# schematic_r2.net
KiCad netlist of a schematic drawn in EAGLE
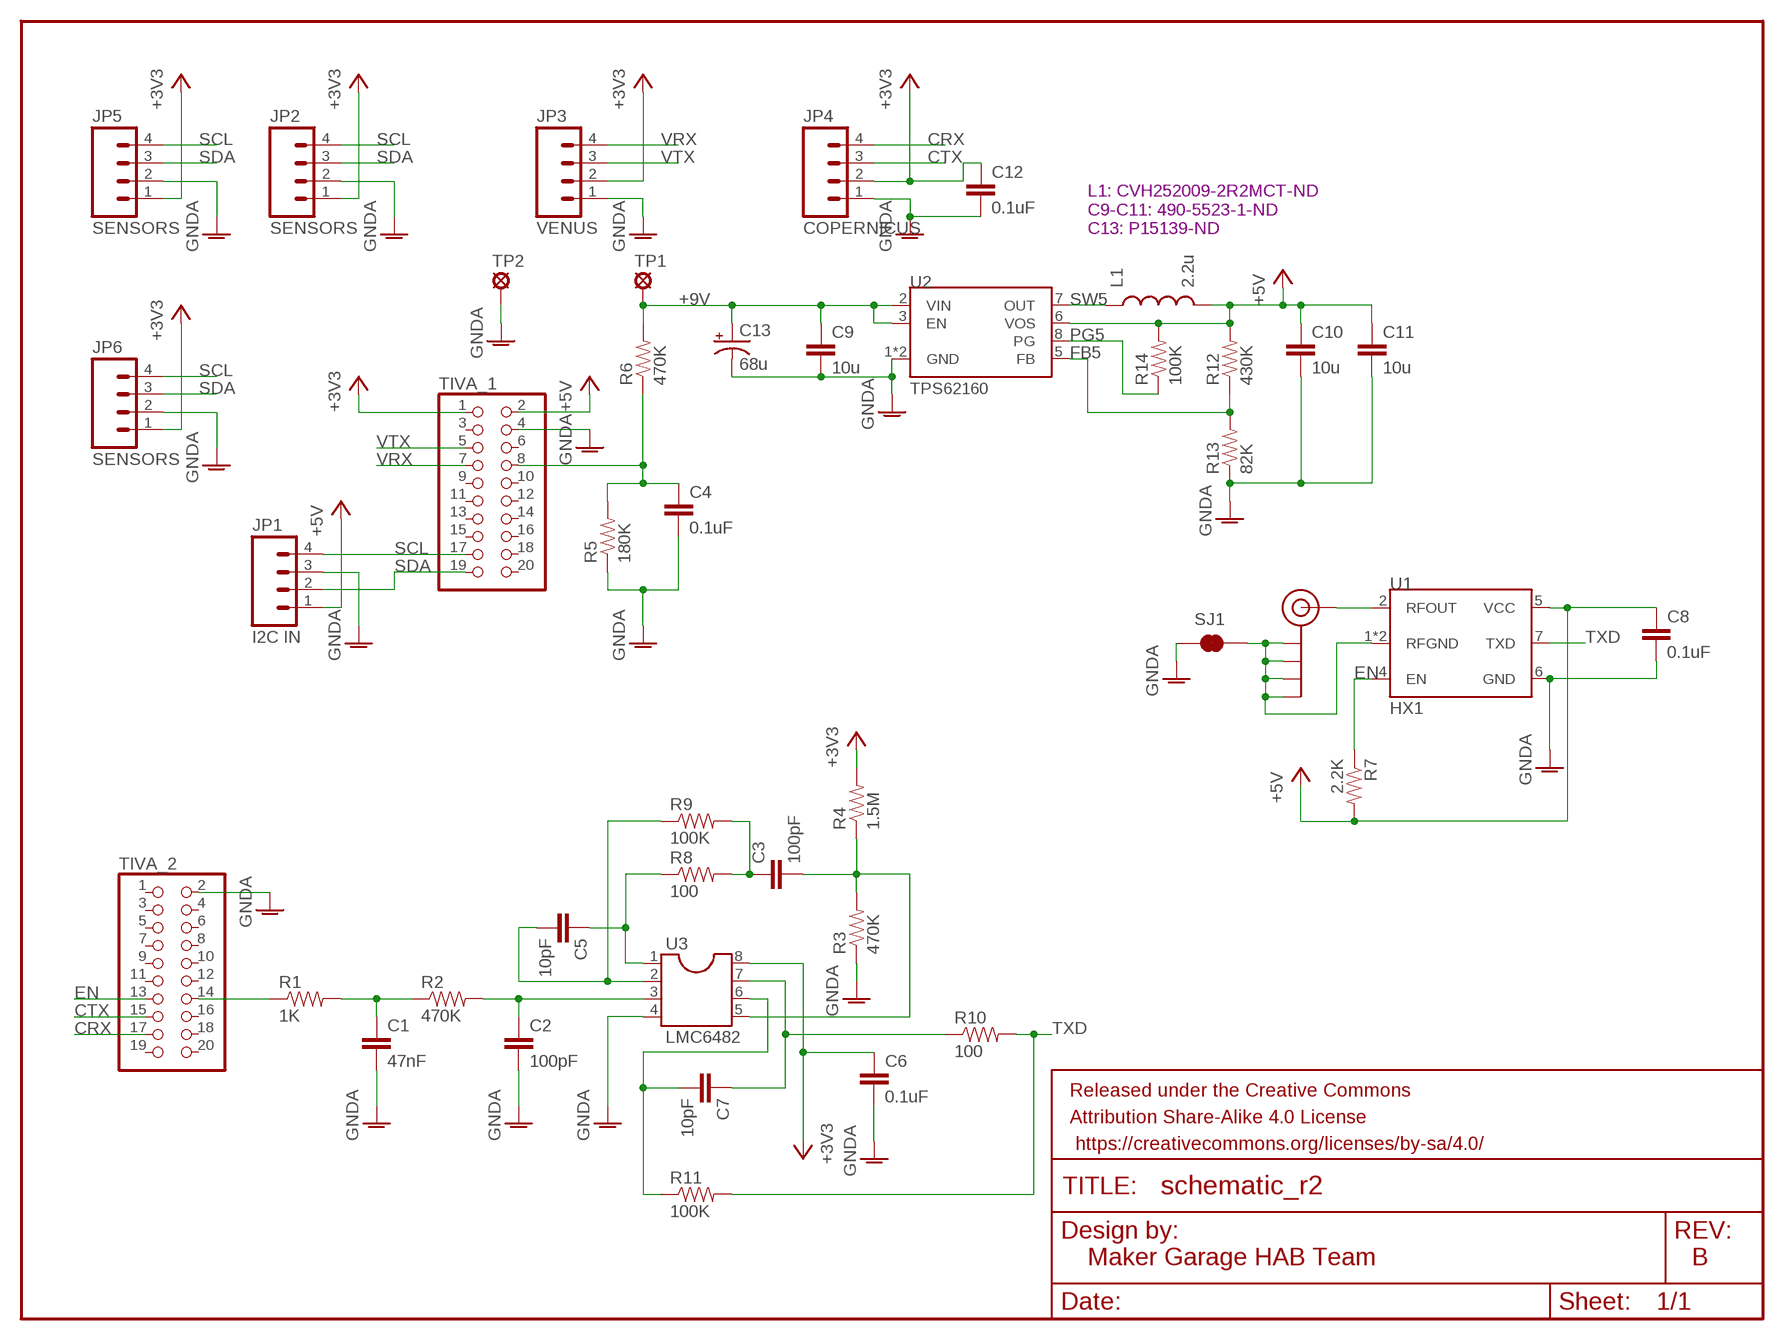
[diagram p0: schematic, sheet 1]

(export (version "E")
  (design (tool "Eeschema 10.0.6"))
  (components
    (comp (ref "C1")
      (value "47nF")
      (footprint "eagle-import:0805")
      (libsource (lib "eagle-import") (part "CAP0805"))
    )
    (comp (ref "C2")
      (value "100pF")
      (footprint "eagle-import:0805")
      (libsource (lib "eagle-import") (part "CAP0805"))
    )
    (comp (ref "C3")
      (value "100pF")
      (footprint "eagle-import:0805")
      (libsource (lib "eagle-import") (part "CAP0805"))
    )
    (comp (ref "C4")
      (value "0.1uF")
      (footprint "eagle-import:0805")
      (libsource (lib "eagle-import") (part "CAP0805"))
    )
    (comp (ref "C5")
      (value "10pF")
      (footprint "eagle-import:0805")
      (libsource (lib "eagle-import") (part "CAP0805"))
    )
    (comp (ref "C6")
      (value "0.1uF")
      (footprint "eagle-import:0805")
      (libsource (lib "eagle-import") (part "CAP0805"))
    )
    (comp (ref "C7")
      (value "10pF")
      (footprint "eagle-import:0805")
      (libsource (lib "eagle-import") (part "CAP0805"))
    )
    (comp (ref "C8")
      (value "0.1uF")
      (footprint "eagle-import:0805")
      (libsource (lib "eagle-import") (part "CAP0805"))
    )
    (comp (ref "C9")
      (value "10u")
      (footprint "eagle-import:0805")
      (libsource (lib "eagle-import") (part "CAP0805"))
    )
    (comp (ref "C10")
      (value "10u")
      (footprint "eagle-import:0805")
      (libsource (lib "eagle-import") (part "CAP0805"))
    )
    (comp (ref "C11")
      (value "10u")
      (footprint "eagle-import:0805")
      (libsource (lib "eagle-import") (part "CAP0805"))
    )
    (comp (ref "C12")
      (value "0.1uF")
      (footprint "eagle-import:0805")
      (libsource (lib "eagle-import") (part "CAP0805"))
    )
    (comp (ref "C13")
      (value "68u")
      (footprint "eagle-import:CPOL-RADIAL-10UF-25V")
      (libsource (lib "eagle-import") (part "CAP_POLPTH2"))
    )
    (comp (ref "FRAME1")
      (value "FRAME-LETTERNO_PACKAGE")
      (footprint "eagle-import:DUMMY")
      (fields (field (name "DESIGNER") "Nobody"))
      (libsource (lib "eagle-import") (part "FRAME-LETTERNO_PACKAGE"))
    )
    (comp (ref "J1")
      (value "SMA_EDGE")
      (footprint "eagle-import:SMA-EDGE")
      (libsource (lib "eagle-import") (part "SMA_EDGE"))
    )
    (comp (ref "JP1")
      (value "I2C IN")
      (footprint "eagle-import:1X04")
      (libsource (lib "eagle-import") (part "M04PTH"))
    )
    (comp (ref "JP2")
      (value "SENSORS")
      (footprint "eagle-import:1X04")
      (libsource (lib "eagle-import") (part "M04PTH"))
    )
    (comp (ref "JP3")
      (value "VENUS")
      (footprint "eagle-import:1X04")
      (libsource (lib "eagle-import") (part "M04PTH"))
    )
    (comp (ref "JP4")
      (value "COPERNICUS")
      (footprint "eagle-import:1X04")
      (libsource (lib "eagle-import") (part "M04PTH"))
    )
    (comp (ref "JP5")
      (value "SENSORS")
      (footprint "eagle-import:1X04")
      (libsource (lib "eagle-import") (part "M04PTH"))
    )
    (comp (ref "JP6")
      (value "SENSORS")
      (footprint "eagle-import:1X04")
      (libsource (lib "eagle-import") (part "M04PTH"))
    )
    (comp (ref "L1")
      (value "2.2u")
      (footprint "eagle-import:1008")
      (libsource (lib "eagle-import") (part "INDUCTOR1008"))
    )
    (comp (ref "R1")
      (value "1K")
      (footprint "eagle-import:0805")
      (libsource (lib "eagle-import") (part "RESISTOR0805-RES"))
    )
    (comp (ref "R2")
      (value "470K")
      (footprint "eagle-import:0805")
      (libsource (lib "eagle-import") (part "RESISTOR0805-RES"))
    )
    (comp (ref "R3")
      (value "470K")
      (footprint "eagle-import:0805")
      (libsource (lib "eagle-import") (part "RESISTOR0805-RES"))
    )
    (comp (ref "R4")
      (value "1.5M")
      (footprint "eagle-import:0805")
      (libsource (lib "eagle-import") (part "RESISTOR0805-RES"))
    )
    (comp (ref "R5")
      (value "180K")
      (footprint "eagle-import:0805")
      (libsource (lib "eagle-import") (part "RESISTOR0805-RES"))
    )
    (comp (ref "R6")
      (value "470K")
      (footprint "eagle-import:0805")
      (libsource (lib "eagle-import") (part "RESISTOR0805-RES"))
    )
    (comp (ref "R7")
      (value "2.2K")
      (footprint "eagle-import:0805")
      (libsource (lib "eagle-import") (part "RESISTOR0805-RES"))
    )
    (comp (ref "R8")
      (value "100")
      (footprint "eagle-import:0805")
      (libsource (lib "eagle-import") (part "RESISTOR0805-RES"))
    )
    (comp (ref "R9")
      (value "100K")
      (footprint "eagle-import:0805")
      (libsource (lib "eagle-import") (part "RESISTOR0805-RES"))
    )
    (comp (ref "R10")
      (value "100")
      (footprint "eagle-import:0805")
      (libsource (lib "eagle-import") (part "RESISTOR0805-RES"))
    )
    (comp (ref "R11")
      (value "100K")
      (footprint "eagle-import:0805")
      (libsource (lib "eagle-import") (part "RESISTOR0805-RES"))
    )
    (comp (ref "R12")
      (value "430K")
      (footprint "eagle-import:0805")
      (libsource (lib "eagle-import") (part "RESISTOR0805-RES"))
    )
    (comp (ref "R13")
      (value "82K")
      (footprint "eagle-import:0805")
      (libsource (lib "eagle-import") (part "RESISTOR0805-RES"))
    )
    (comp (ref "R14")
      (value "100K")
      (footprint "eagle-import:0805")
      (libsource (lib "eagle-import") (part "RESISTOR0805-RES"))
    )
    (comp (ref "SJ1")
      (value "JUMPER-PAD-2-NC_BY_TRACE")
      (footprint "eagle-import:PAD-JUMPER-2-NC_BY_TRACE_YES_SILK")
      (libsource (lib "eagle-import") (part "JUMPER-PAD-2-NC_BY_TRACE"))
    )
    (comp (ref "TIVA_1")
      (value "PINHD-2X10")
      (footprint "eagle-import:2X10")
      (libsource (lib "eagle-import") (part "PINHD-2X10"))
    )
    (comp (ref "TIVA_2")
      (value "PINHD-2X10")
      (footprint "eagle-import:2X10")
      (libsource (lib "eagle-import") (part "PINHD-2X10"))
    )
    (comp (ref "TP1")
      (value "MCS08")
      (footprint "eagle-import:MCS08")
      (libsource (lib "eagle-import") (part "MCS08"))
    )
    (comp (ref "TP2")
      (value "MCS08")
      (footprint "eagle-import:MCS08")
      (libsource (lib "eagle-import") (part "MCS08"))
    )
    (comp (ref "U1")
      (value "HX1")
      (footprint "eagle-import:1X12")
      (libsource (lib "eagle-import") (part "HX1"))
    )
    (comp (ref "U2")
      (value "TPS62160")
      (footprint "eagle-import:MSOP8")
      (libsource (lib "eagle-import") (part "TPS62160"))
    )
    (comp (ref "U3")
      (value "LMC6482")
      (footprint "eagle-import:DIL08")
      (libsource (lib "eagle-import") (part "DIL8"))
    )
  )
  (nets
    (net (code "1") (name "+3V3") (class "Default")
      (node (ref "C12") (pin "1") (pinfunction "1_1") (pintype "passive"))
      (node (ref "C6") (pin "1") (pinfunction "1_1") (pintype "passive"))
      (node (ref "JP2") (pin "1") (pinfunction "1_1") (pintype "passive"))
      (node (ref "JP3") (pin "2") (pinfunction "2_2") (pintype "passive"))
      (node (ref "JP4") (pin "2") (pinfunction "2_2") (pintype "passive"))
      (node (ref "JP5") (pin "1") (pinfunction "1_1") (pintype "passive"))
      (node (ref "JP6") (pin "1") (pinfunction "1_1") (pintype "passive"))
      (node (ref "R4") (pin "2") (pinfunction "2_2") (pintype "passive"))
      (node (ref "TIVA_1") (pin "1") (pinfunction "1_1") (pintype "passive"))
      (node (ref "U3") (pin "8") (pinfunction "8_8") (pintype "passive"))
    )
    (net (code "2") (name "+5V") (class "Default")
      (node (ref "C10") (pin "1") (pinfunction "1_1") (pintype "passive"))
      (node (ref "C11") (pin "1") (pinfunction "1_1") (pintype "passive"))
      (node (ref "C8") (pin "1") (pinfunction "1_1") (pintype "passive"))
      (node (ref "JP1") (pin "1") (pinfunction "1_1") (pintype "passive"))
      (node (ref "L1") (pin "2") (pinfunction "2_2") (pintype "passive"))
      (node (ref "R12") (pin "2") (pinfunction "2_2") (pintype "passive"))
      (node (ref "R14") (pin "2") (pinfunction "2_2") (pintype "passive"))
      (node (ref "R7") (pin "2") (pinfunction "2_2") (pintype "passive"))
      (node (ref "TIVA_1") (pin "2") (pinfunction "2_2") (pintype "passive"))
      (node (ref "U1") (pin "5") (pinfunction "VCC_5") (pintype "power_in"))
      (node (ref "U2") (pin "6") (pinfunction "VOS_6") (pintype "input"))
    )
    (net (code "3") (name "/+9V") (class "Default")
      (node (ref "C13") (pin "1") (pinfunction "+_1") (pintype "passive"))
      (node (ref "C9") (pin "1") (pinfunction "1_1") (pintype "passive"))
      (node (ref "R6") (pin "2") (pinfunction "2_2") (pintype "passive"))
      (node (ref "TP1") (pin "MP") (pinfunction "MP_MP") (pintype "passive"))
      (node (ref "U2") (pin "2") (pinfunction "VIN_2") (pintype "power_in"))
      (node (ref "U2") (pin "3") (pinfunction "EN_3") (pintype "input"))
    )
    (net (code "4") (name "/CRX") (class "Default")
      (node (ref "JP4") (pin "4") (pinfunction "4_4") (pintype "passive"))
      (node (ref "TIVA_2") (pin "17") (pinfunction "17_17") (pintype "passive"))
    )
    (net (code "5") (name "/CTX") (class "Default")
      (node (ref "JP4") (pin "3") (pinfunction "3_3") (pintype "passive"))
      (node (ref "TIVA_2") (pin "15") (pinfunction "15_15") (pintype "passive"))
    )
    (net (code "6") (name "/EN") (class "Default")
      (node (ref "R7") (pin "1") (pinfunction "1_1") (pintype "passive"))
      (node (ref "TIVA_2") (pin "13") (pinfunction "13_13") (pintype "passive"))
      (node (ref "U1") (pin "4") (pinfunction "EN_4") (pintype "input"))
    )
    (net (code "7") (name "/FB5") (class "Default")
      (node (ref "R12") (pin "1") (pinfunction "1_1") (pintype "passive"))
      (node (ref "R13") (pin "2") (pinfunction "2_2") (pintype "passive"))
      (node (ref "U2") (pin "5") (pinfunction "FB_5") (pintype "input"))
    )
    (net (code "8") (name "/PG5") (class "Default")
      (node (ref "R14") (pin "1") (pinfunction "1_1") (pintype "passive"))
      (node (ref "U2") (pin "8") (pinfunction "PG_8") (pintype "open_collector"))
    )
    (net (code "9") (name "/SCL") (class "Default")
      (node (ref "JP1") (pin "4") (pinfunction "4_4") (pintype "passive"))
      (node (ref "JP2") (pin "4") (pinfunction "4_4") (pintype "passive"))
      (node (ref "JP5") (pin "4") (pinfunction "4_4") (pintype "passive"))
      (node (ref "JP6") (pin "4") (pinfunction "4_4") (pintype "passive"))
      (node (ref "TIVA_1") (pin "17") (pinfunction "17_17") (pintype "passive"))
    )
    (net (code "10") (name "/SDA") (class "Default")
      (node (ref "JP1") (pin "2") (pinfunction "2_2") (pintype "passive"))
      (node (ref "JP2") (pin "3") (pinfunction "3_3") (pintype "passive"))
      (node (ref "JP5") (pin "3") (pinfunction "3_3") (pintype "passive"))
      (node (ref "JP6") (pin "3") (pinfunction "3_3") (pintype "passive"))
      (node (ref "TIVA_1") (pin "19") (pinfunction "19_19") (pintype "passive"))
    )
    (net (code "11") (name "/SW5") (class "Default")
      (node (ref "L1") (pin "1") (pinfunction "1_1") (pintype "passive"))
      (node (ref "U2") (pin "7") (pinfunction "OUT_7") (pintype "output"))
    )
    (net (code "12") (name "/TXD") (class "Default")
      (node (ref "R10") (pin "2") (pinfunction "2_2") (pintype "passive"))
      (node (ref "R11") (pin "2") (pinfunction "2_2") (pintype "passive"))
      (node (ref "U1") (pin "7") (pinfunction "TXD_7") (pintype "input"))
    )
    (net (code "13") (name "/VRX") (class "Default")
      (node (ref "JP3") (pin "4") (pinfunction "4_4") (pintype "passive"))
      (node (ref "TIVA_1") (pin "7") (pinfunction "7_7") (pintype "passive"))
    )
    (net (code "14") (name "/VTX") (class "Default")
      (node (ref "JP3") (pin "3") (pinfunction "3_3") (pintype "passive"))
      (node (ref "TIVA_1") (pin "5") (pinfunction "5_5") (pintype "passive"))
    )
    (net (code "15") (name "GNDA") (class "Default")
      (node (ref "C1") (pin "2") (pinfunction "2_2") (pintype "passive"))
      (node (ref "C10") (pin "2") (pinfunction "2_2") (pintype "passive"))
      (node (ref "C11") (pin "2") (pinfunction "2_2") (pintype "passive"))
      (node (ref "C12") (pin "2") (pinfunction "2_2") (pintype "passive"))
      (node (ref "C13") (pin "2") (pinfunction "-_2") (pintype "passive"))
      (node (ref "C2") (pin "2") (pinfunction "2_2") (pintype "passive"))
      (node (ref "C4") (pin "2") (pinfunction "2_2") (pintype "passive"))
      (node (ref "C6") (pin "2") (pinfunction "2_2") (pintype "passive"))
      (node (ref "C8") (pin "2") (pinfunction "2_2") (pintype "passive"))
      (node (ref "C9") (pin "2") (pinfunction "2_2") (pintype "passive"))
      (node (ref "JP1") (pin "3") (pinfunction "3_3") (pintype "passive"))
      (node (ref "JP2") (pin "2") (pinfunction "2_2") (pintype "passive"))
      (node (ref "JP3") (pin "1") (pinfunction "1_1") (pintype "passive"))
      (node (ref "JP4") (pin "1") (pinfunction "1_1") (pintype "passive"))
      (node (ref "JP5") (pin "2") (pinfunction "2_2") (pintype "passive"))
      (node (ref "JP6") (pin "2") (pinfunction "2_2") (pintype "passive"))
      (node (ref "R13") (pin "1") (pinfunction "1_1") (pintype "passive"))
      (node (ref "R3") (pin "1") (pinfunction "1_1") (pintype "passive"))
      (node (ref "R5") (pin "1") (pinfunction "1_1") (pintype "passive"))
      (node (ref "SJ1") (pin "1") (pinfunction "1_1") (pintype "passive"))
      (node (ref "TIVA_1") (pin "4") (pinfunction "4_4") (pintype "passive"))
      (node (ref "TIVA_2") (pin "2") (pinfunction "2_2") (pintype "passive"))
      (node (ref "TP2") (pin "MP") (pinfunction "MP_MP") (pintype "passive"))
      (node (ref "U1") (pin "6") (pinfunction "GND_6") (pintype "power_in"))
      (node (ref "U2") (pin "1") (pinfunction "GND_1") (pintype "power_in"))
      (node (ref "U2") (pin "4") (pinfunction "GND_4") (pintype "power_in"))
      (node (ref "U3") (pin "4") (pinfunction "4_4") (pintype "passive"))
    )
    (net (code "16") (name "Net-(C1-Pad1)") (class "Default")
      (node (ref "C1") (pin "1") (pinfunction "1_1") (pintype "passive"))
      (node (ref "R1") (pin "2") (pinfunction "2_2") (pintype "passive"))
      (node (ref "R2") (pin "1") (pinfunction "1_1") (pintype "passive"))
    )
    (net (code "17") (name "Net-(C2-Pad1)") (class "Default")
      (node (ref "C2") (pin "1") (pinfunction "1_1") (pintype "passive"))
      (node (ref "R2") (pin "2") (pinfunction "2_2") (pintype "passive"))
      (node (ref "U3") (pin "3") (pinfunction "3_3") (pintype "passive"))
    )
    (net (code "18") (name "Net-(C3-Pad1)") (class "Default")
      (node (ref "C3") (pin "1") (pinfunction "1_1") (pintype "passive"))
      (node (ref "R8") (pin "2") (pinfunction "2_2") (pintype "passive"))
      (node (ref "R9") (pin "2") (pinfunction "2_2") (pintype "passive"))
    )
    (net (code "19") (name "Net-(C3-Pad2)") (class "Default")
      (node (ref "C3") (pin "2") (pinfunction "2_2") (pintype "passive"))
      (node (ref "R3") (pin "2") (pinfunction "2_2") (pintype "passive"))
      (node (ref "R4") (pin "1") (pinfunction "1_1") (pintype "passive"))
      (node (ref "U3") (pin "5") (pinfunction "5_5") (pintype "passive"))
    )
    (net (code "20") (name "Net-(C4-Pad1)") (class "Default")
      (node (ref "C4") (pin "1") (pinfunction "1_1") (pintype "passive"))
      (node (ref "R5") (pin "2") (pinfunction "2_2") (pintype "passive"))
      (node (ref "R6") (pin "1") (pinfunction "1_1") (pintype "passive"))
      (node (ref "TIVA_1") (pin "8") (pinfunction "8_8") (pintype "passive"))
    )
    (net (code "21") (name "Net-(C5-Pad1)") (class "Default")
      (node (ref "C5") (pin "1") (pinfunction "1_1") (pintype "passive"))
      (node (ref "R8") (pin "1") (pinfunction "1_1") (pintype "passive"))
      (node (ref "U3") (pin "1") (pinfunction "1_1") (pintype "passive"))
    )
    (net (code "22") (name "Net-(C5-Pad2)") (class "Default")
      (node (ref "C5") (pin "2") (pinfunction "2_2") (pintype "passive"))
      (node (ref "R9") (pin "1") (pinfunction "1_1") (pintype "passive"))
      (node (ref "U3") (pin "2") (pinfunction "2_2") (pintype "passive"))
    )
    (net (code "23") (name "Net-(C7-Pad1)") (class "Default")
      (node (ref "C7") (pin "1") (pinfunction "1_1") (pintype "passive"))
      (node (ref "R10") (pin "1") (pinfunction "1_1") (pintype "passive"))
      (node (ref "U3") (pin "7") (pinfunction "7_7") (pintype "passive"))
    )
    (net (code "24") (name "Net-(C7-Pad2)") (class "Default")
      (node (ref "C7") (pin "2") (pinfunction "2_2") (pintype "passive"))
      (node (ref "R11") (pin "1") (pinfunction "1_1") (pintype "passive"))
      (node (ref "U3") (pin "6") (pinfunction "6_6") (pintype "passive"))
    )
    (net (code "25") (name "Net-(J1-GND-PadGND@0)") (class "Default")
      (node (ref "J1") (pin "GND@0") (pinfunction "GND_GND@0") (pintype "bidirectional"))
      (node (ref "J1") (pin "GND@1") (pinfunction "GND_GND@1") (pintype "bidirectional"))
      (node (ref "J1") (pin "GND@2") (pinfunction "GND_GND@2") (pintype "bidirectional"))
      (node (ref "J1") (pin "GND@3") (pinfunction "GND_GND@3") (pintype "bidirectional"))
      (node (ref "SJ1") (pin "2") (pinfunction "2_2") (pintype "passive"))
      (node (ref "U1") (pin "1") (pinfunction "RFGND_1") (pintype "power_in"))
      (node (ref "U1") (pin "3") (pinfunction "RFGND_3") (pintype "power_in"))
    )
    (net (code "26") (name "Net-(J1-SIGNAL)") (class "Default")
      (node (ref "J1") (pin "SIG") (pinfunction "SIGNAL_SIG") (pintype "bidirectional"))
      (node (ref "U1") (pin "2") (pinfunction "RFOUT_2") (pintype "output"))
    )
    (net (code "27") (name "Net-(R1-Pad1)") (class "Default")
      (node (ref "R1") (pin "1") (pinfunction "1_1") (pintype "passive"))
      (node (ref "TIVA_2") (pin "14") (pinfunction "14_14") (pintype "passive"))
    )
    (net (code "28") (name "unconnected-(TIVA_1-Pad3)") (class "Default")
      (node (ref "TIVA_1") (pin "3") (pinfunction "3_3") (pintype "passive"))
    )
    (net (code "29") (name "unconnected-(TIVA_1-Pad6)") (class "Default")
      (node (ref "TIVA_1") (pin "6") (pinfunction "6_6") (pintype "passive"))
    )
    (net (code "30") (name "unconnected-(TIVA_1-Pad9)") (class "Default")
      (node (ref "TIVA_1") (pin "9") (pinfunction "9_9") (pintype "passive"))
    )
    (net (code "31") (name "unconnected-(TIVA_1-Pad10)") (class "Default")
      (node (ref "TIVA_1") (pin "10") (pinfunction "10_10") (pintype "passive"))
    )
    (net (code "32") (name "unconnected-(TIVA_1-Pad11)") (class "Default")
      (node (ref "TIVA_1") (pin "11") (pinfunction "11_11") (pintype "passive"))
    )
    (net (code "33") (name "unconnected-(TIVA_1-Pad12)") (class "Default")
      (node (ref "TIVA_1") (pin "12") (pinfunction "12_12") (pintype "passive"))
    )
    (net (code "34") (name "unconnected-(TIVA_1-Pad13)") (class "Default")
      (node (ref "TIVA_1") (pin "13") (pinfunction "13_13") (pintype "passive"))
    )
    (net (code "35") (name "unconnected-(TIVA_1-Pad14)") (class "Default")
      (node (ref "TIVA_1") (pin "14") (pinfunction "14_14") (pintype "passive"))
    )
    (net (code "36") (name "unconnected-(TIVA_1-Pad15)") (class "Default")
      (node (ref "TIVA_1") (pin "15") (pinfunction "15_15") (pintype "passive"))
    )
    (net (code "37") (name "unconnected-(TIVA_1-Pad16)") (class "Default")
      (node (ref "TIVA_1") (pin "16") (pinfunction "16_16") (pintype "passive"))
    )
    (net (code "38") (name "unconnected-(TIVA_1-Pad18)") (class "Default")
      (node (ref "TIVA_1") (pin "18") (pinfunction "18_18") (pintype "passive"))
    )
    (net (code "39") (name "unconnected-(TIVA_1-Pad20)") (class "Default")
      (node (ref "TIVA_1") (pin "20") (pinfunction "20_20") (pintype "passive"))
    )
    (net (code "40") (name "unconnected-(TIVA_2-Pad1)") (class "Default")
      (node (ref "TIVA_2") (pin "1") (pinfunction "1_1") (pintype "passive"))
    )
    (net (code "41") (name "unconnected-(TIVA_2-Pad3)") (class "Default")
      (node (ref "TIVA_2") (pin "3") (pinfunction "3_3") (pintype "passive"))
    )
    (net (code "42") (name "unconnected-(TIVA_2-Pad4)") (class "Default")
      (node (ref "TIVA_2") (pin "4") (pinfunction "4_4") (pintype "passive"))
    )
    (net (code "43") (name "unconnected-(TIVA_2-Pad5)") (class "Default")
      (node (ref "TIVA_2") (pin "5") (pinfunction "5_5") (pintype "passive"))
    )
    (net (code "44") (name "unconnected-(TIVA_2-Pad6)") (class "Default")
      (node (ref "TIVA_2") (pin "6") (pinfunction "6_6") (pintype "passive"))
    )
    (net (code "45") (name "unconnected-(TIVA_2-Pad7)") (class "Default")
      (node (ref "TIVA_2") (pin "7") (pinfunction "7_7") (pintype "passive"))
    )
    (net (code "46") (name "unconnected-(TIVA_2-Pad8)") (class "Default")
      (node (ref "TIVA_2") (pin "8") (pinfunction "8_8") (pintype "passive"))
    )
    (net (code "47") (name "unconnected-(TIVA_2-Pad9)") (class "Default")
      (node (ref "TIVA_2") (pin "9") (pinfunction "9_9") (pintype "passive"))
    )
    (net (code "48") (name "unconnected-(TIVA_2-Pad10)") (class "Default")
      (node (ref "TIVA_2") (pin "10") (pinfunction "10_10") (pintype "passive"))
    )
    (net (code "49") (name "unconnected-(TIVA_2-Pad11)") (class "Default")
      (node (ref "TIVA_2") (pin "11") (pinfunction "11_11") (pintype "passive"))
    )
    (net (code "50") (name "unconnected-(TIVA_2-Pad12)") (class "Default")
      (node (ref "TIVA_2") (pin "12") (pinfunction "12_12") (pintype "passive"))
    )
    (net (code "51") (name "unconnected-(TIVA_2-Pad16)") (class "Default")
      (node (ref "TIVA_2") (pin "16") (pinfunction "16_16") (pintype "passive"))
    )
    (net (code "52") (name "unconnected-(TIVA_2-Pad18)") (class "Default")
      (node (ref "TIVA_2") (pin "18") (pinfunction "18_18") (pintype "passive"))
    )
    (net (code "53") (name "unconnected-(TIVA_2-Pad19)") (class "Default")
      (node (ref "TIVA_2") (pin "19") (pinfunction "19_19") (pintype "passive"))
    )
    (net (code "54") (name "unconnected-(TIVA_2-Pad20)") (class "Default")
      (node (ref "TIVA_2") (pin "20") (pinfunction "20_20") (pintype "passive"))
    )
  )
)
